# 60-hv-amp-soft-start.net
KiCad netlist of a schematic drawn in EAGLE
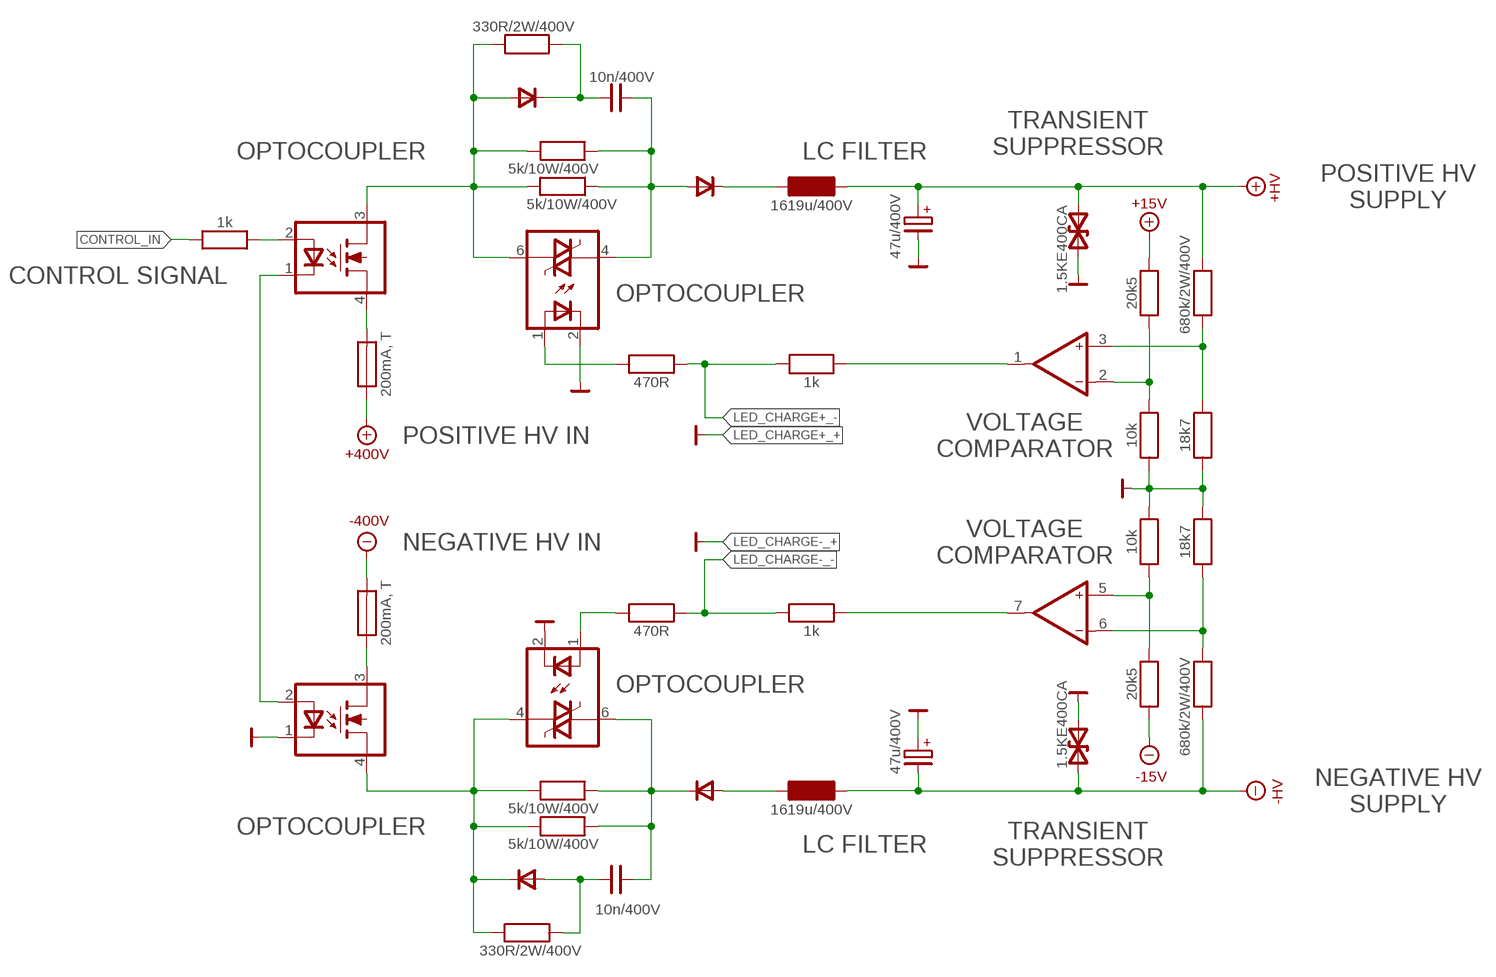
[diagram p0: schematic, sheet 1]

(export (version "E")
  (design (tool "Eeschema 10.0.6"))
  (components
    (comp (ref "C25")
      (value "10n/400V")
      (footprint "eagle-import:C03-CERAMIC-HV15-N")
      (libsource (lib "eagle-import") (part "C03-CERAMIC-HV15-N"))
    )
    (comp (ref "C26")
      (value "10n/400V")
      (footprint "eagle-import:C03-CERAMIC-HV15-N")
      (libsource (lib "eagle-import") (part "C03-CERAMIC-HV15-N"))
    )
    (comp (ref "C27")
      (value "47u/400V")
      (footprint "eagle-import:CE03-R18")
      (libsource (lib "eagle-import") (part "CE03-R18"))
    )
    (comp (ref "C28")
      (value "47u/400V")
      (footprint "eagle-import:CE03-R18")
      (libsource (lib "eagle-import") (part "CE03-R18"))
    )
    (comp (ref "D27")
      (value "UF4007")
      (footprint "eagle-import:D04N-DO41-VALUE")
      (libsource (lib "eagle-import") (part "D04B"))
    )
    (comp (ref "D28")
      (value "UF4007")
      (footprint "eagle-import:D04N-DO41-VALUE")
      (libsource (lib "eagle-import") (part "D04B"))
    )
    (comp (ref "D29")
      (value "UF4007")
      (footprint "eagle-import:D04N-DO41-VALUE")
      (libsource (lib "eagle-import") (part "D04B"))
    )
    (comp (ref "D30")
      (value "UF4007")
      (footprint "eagle-import:D04N-DO41-VALUE")
      (libsource (lib "eagle-import") (part "D04B"))
    )
    (comp (ref "D31")
      (value "1.5KE400CA")
      (footprint "eagle-import:DSB06N2")
      (libsource (lib "eagle-import") (part "DSB"))
    )
    (comp (ref "D32")
      (value "1.5KE400CA")
      (footprint "eagle-import:DSB06N2")
      (libsource (lib "eagle-import") (part "DSB"))
    )
    (comp (ref "F1")
      (value "200mA, T")
      (footprint "eagle-import:F02")
      (libsource (lib "eagle-import") (part "F"))
    )
    (comp (ref "F2")
      (value "200mA, T")
      (footprint "eagle-import:F02")
      (libsource (lib "eagle-import") (part "F"))
    )
    (comp (ref "L1")
      (value "1619u/400V")
      (footprint "eagle-import:L12-6X26")
      (libsource (lib "eagle-import") (part "L12-6X26"))
    )
    (comp (ref "L2")
      (value "1619u/400V")
      (footprint "eagle-import:L12-6X26")
      (libsource (lib "eagle-import") (part "L12-6X26"))
    )
    (comp (ref "N25")
      (value "AQZ204")
      (footprint "eagle-import:AQZ-N")
      (libsource (lib "eagle-import") (part "AQZ202"))
    )
    (comp (ref "N26")
      (value "AQZ204")
      (footprint "eagle-import:AQZ-N")
      (libsource (lib "eagle-import") (part "AQZ202"))
    )
    (comp (ref "N27")
      (value "IL420")
      (footprint "eagle-import:DIP06L")
      (libsource (lib "eagle-import") (part "IL420"))
    )
    (comp (ref "N28")
      (value "IL420")
      (footprint "eagle-import:DIP06L")
      (libsource (lib "eagle-import") (part "IL420"))
    )
    (comp (ref "N29")
      (value "OPA2277")
      (footprint "eagle-import:DIP08L")
      (libsource (lib "eagle-import") (part "OPA2277L"))
    )
    (comp (ref "R113")
      (value "1k")
      (footprint "eagle-import:R04N")
      (libsource (lib "eagle-import") (part "R04"))
    )
    (comp (ref "R114")
      (value "330R/2W/400V")
      (footprint "eagle-import:R06-2W")
      (libsource (lib "eagle-import") (part "R06-2W"))
    )
    (comp (ref "R115")
      (value "5k/10W/400V")
      (footprint "eagle-import:TO220-2A")
      (libsource (lib "eagle-import") (part "R02A"))
    )
    (comp (ref "R116")
      (value "5k/10W/400V")
      (footprint "eagle-import:TO220-2A")
      (libsource (lib "eagle-import") (part "R02A"))
    )
    (comp (ref "R117")
      (value "5k/10W/400V")
      (footprint "eagle-import:TO220-2A")
      (libsource (lib "eagle-import") (part "R02A"))
    )
    (comp (ref "R118")
      (value "5k/10W/400V")
      (footprint "eagle-import:TO220-2A")
      (libsource (lib "eagle-import") (part "R02A"))
    )
    (comp (ref "R119")
      (value "330R/2W/400V")
      (footprint "eagle-import:R06-2W")
      (libsource (lib "eagle-import") (part "R06-2W"))
    )
    (comp (ref "R120")
      (value "470R")
      (footprint "eagle-import:R04N")
      (libsource (lib "eagle-import") (part "R04N"))
    )
    (comp (ref "R121")
      (value "470R")
      (footprint "eagle-import:R04N")
      (libsource (lib "eagle-import") (part "R04N"))
    )
    (comp (ref "R122")
      (value "1k")
      (footprint "eagle-import:R04N")
      (libsource (lib "eagle-import") (part "R04N"))
    )
    (comp (ref "R123")
      (value "1k")
      (footprint "eagle-import:R04N")
      (libsource (lib "eagle-import") (part "R04N"))
    )
    (comp (ref "R124")
      (value "20k5")
      (footprint "eagle-import:R04N")
      (libsource (lib "eagle-import") (part "R04N"))
    )
    (comp (ref "R125")
      (value "10k")
      (footprint "eagle-import:R04N")
      (libsource (lib "eagle-import") (part "R"))
    )
    (comp (ref "R126")
      (value "10k")
      (footprint "eagle-import:R04N")
      (libsource (lib "eagle-import") (part "R04N"))
    )
    (comp (ref "R127")
      (value "20k5")
      (footprint "eagle-import:R04N")
      (libsource (lib "eagle-import") (part "R04N"))
    )
    (comp (ref "R128")
      (value "680k/2W/400V")
      (footprint "eagle-import:R06-2W")
      (libsource (lib "eagle-import") (part "R06-2W"))
    )
    (comp (ref "R129")
      (value "18k7")
      (footprint "eagle-import:R04N")
      (libsource (lib "eagle-import") (part "R04N"))
    )
    (comp (ref "R130")
      (value "18k7")
      (footprint "eagle-import:R04N")
      (libsource (lib "eagle-import") (part "R04N"))
    )
    (comp (ref "R131")
      (value "680k/2W/400V")
      (footprint "eagle-import:R06-2W")
      (libsource (lib "eagle-import") (part "R06-2W"))
    )
  )
  (nets
    (net (code "1") (name "CONTROL_IN") (class "Default")
      (node (ref "R113") (pin "1") (pinfunction "1_1") (pintype "passive"))
    )
    (net (code "2") (name "LED_CHARGE+_+") (class "Default")
      (node (ref "C27") (pin "-") (pinfunction "-_-") (pintype "passive"))
      (node (ref "C28") (pin "+") (pinfunction "+_+") (pintype "passive"))
      (node (ref "D31") (pin "1") (pinfunction "1_1") (pintype "passive"))
      (node (ref "D32") (pin "2") (pinfunction "2_2") (pintype "passive"))
      (node (ref "N26") (pin "1") (pinfunction "C_1") (pintype "passive"))
      (node (ref "N27") (pin "2") (pinfunction "C_2") (pintype "passive"))
      (node (ref "N28") (pin "2") (pinfunction "C_2") (pintype "passive"))
      (node (ref "R125") (pin "1") (pinfunction "1_1") (pintype "passive"))
      (node (ref "R126") (pin "2") (pinfunction "2_2") (pintype "passive"))
      (node (ref "R129") (pin "1") (pinfunction "1_1") (pintype "passive"))
      (node (ref "R130") (pin "2") (pinfunction "2_2") (pintype "passive"))
    )
    (net (code "3") (name "LED_CHARGE+_-") (class "Default")
      (node (ref "R120") (pin "2") (pinfunction "2_2") (pintype "passive"))
      (node (ref "R122") (pin "2") (pinfunction "2_2") (pintype "passive"))
    )
    (net (code "4") (name "LED_CHARGE-_-") (class "Default")
      (node (ref "R121") (pin "2") (pinfunction "2_2") (pintype "passive"))
      (node (ref "R123") (pin "2") (pinfunction "2_2") (pintype "passive"))
    )
    (net (code "5") (name "Net-(C25-Pad1)") (class "Default")
      (node (ref "C25") (pin "1") (pinfunction "1_1") (pintype "passive"))
      (node (ref "D28") (pin "A") (pinfunction "A_A") (pintype "passive"))
      (node (ref "R119") (pin "1") (pinfunction "1_1") (pintype "passive"))
    )
    (net (code "6") (name "Net-(C26-Pad1)") (class "Default")
      (node (ref "C26") (pin "1") (pinfunction "1_1") (pintype "passive"))
      (node (ref "D27") (pin "C") (pinfunction "C_C") (pintype "passive"))
      (node (ref "R114") (pin "2") (pinfunction "2_2") (pintype "passive"))
    )
    (net (code "7") (name "Net-(D29-PadC)") (class "Default")
      (node (ref "D29") (pin "C") (pinfunction "C_C") (pintype "passive"))
      (node (ref "L1") (pin "1") (pinfunction "1_1") (pintype "passive"))
    )
    (net (code "8") (name "Net-(D30-PadA)") (class "Default")
      (node (ref "D30") (pin "A") (pinfunction "A_A") (pintype "passive"))
      (node (ref "L2") (pin "1") (pinfunction "1_1") (pintype "passive"))
    )
    (net (code "9") (name "Net-(N25-A)") (class "Default")
      (node (ref "N25") (pin "2") (pinfunction "A_2") (pintype "passive"))
      (node (ref "R113") (pin "2") (pinfunction "2_2") (pintype "passive"))
    )
    (net (code "10") (name "Net-(N25-C)") (class "Default")
      (node (ref "N25") (pin "1") (pinfunction "C_1") (pintype "passive"))
      (node (ref "N26") (pin "2") (pinfunction "A_2") (pintype "passive"))
    )
    (net (code "11") (name "Net-(N25-OUT1)") (class "Default")
      (node (ref "D27") (pin "A") (pinfunction "A_A") (pintype "passive"))
      (node (ref "N25") (pin "3") (pinfunction "OUT1_3") (pintype "passive"))
      (node (ref "N27") (pin "6") (pinfunction "MT2_6") (pintype "passive"))
      (node (ref "R114") (pin "1") (pinfunction "1_1") (pintype "passive"))
      (node (ref "R115") (pin "1") (pinfunction "1_1") (pintype "passive"))
      (node (ref "R116") (pin "2") (pinfunction "2_2") (pintype "passive"))
    )
    (net (code "12") (name "Net-(N25-OUT2)") (class "Default")
      (node (ref "F1") (pin "2") (pinfunction "2_2") (pintype "passive"))
      (node (ref "N25") (pin "4") (pinfunction "OUT2_4") (pintype "passive"))
    )
    (net (code "13") (name "Net-(N26-OUT1)") (class "Default")
      (node (ref "F2") (pin "1") (pinfunction "1_1") (pintype "passive"))
      (node (ref "N26") (pin "3") (pinfunction "OUT1_3") (pintype "passive"))
    )
    (net (code "14") (name "Net-(N26-OUT2)") (class "Default")
      (node (ref "D28") (pin "C") (pinfunction "C_C") (pintype "passive"))
      (node (ref "N26") (pin "4") (pinfunction "OUT2_4") (pintype "passive"))
      (node (ref "N28") (pin "4") (pinfunction "MT1_4") (pintype "passive"))
      (node (ref "R117") (pin "2") (pinfunction "2_2") (pintype "passive"))
      (node (ref "R118") (pin "1") (pinfunction "1_1") (pintype "passive"))
      (node (ref "R119") (pin "2") (pinfunction "2_2") (pintype "passive"))
    )
    (net (code "15") (name "Net-(N27-A)") (class "Default")
      (node (ref "N27") (pin "1") (pinfunction "A_1") (pintype "passive"))
      (node (ref "R120") (pin "1") (pinfunction "1_1") (pintype "passive"))
    )
    (net (code "16") (name "Net-(N27-MT1)") (class "Default")
      (node (ref "C26") (pin "2") (pinfunction "2_2") (pintype "passive"))
      (node (ref "D29") (pin "A") (pinfunction "A_A") (pintype "passive"))
      (node (ref "N27") (pin "4") (pinfunction "MT1_4") (pintype "passive"))
      (node (ref "R115") (pin "2") (pinfunction "2_2") (pintype "passive"))
      (node (ref "R116") (pin "1") (pinfunction "1_1") (pintype "passive"))
    )
    (net (code "17") (name "Net-(N28-A)") (class "Default")
      (node (ref "N28") (pin "1") (pinfunction "A_1") (pintype "passive"))
      (node (ref "R121") (pin "1") (pinfunction "1_1") (pintype "passive"))
    )
    (net (code "18") (name "Net-(N28-MT2)") (class "Default")
      (node (ref "C25") (pin "2") (pinfunction "2_2") (pintype "passive"))
      (node (ref "D30") (pin "C") (pinfunction "C_C") (pintype "passive"))
      (node (ref "N28") (pin "6") (pinfunction "MT2_6") (pintype "passive"))
      (node (ref "R117") (pin "1") (pinfunction "1_1") (pintype "passive"))
      (node (ref "R118") (pin "2") (pinfunction "2_2") (pintype "passive"))
    )
    (net (code "19") (name "Net-(N29A-IN+)") (class "Default")
      (node (ref "N29") (pin "3") (pinfunction "IN+_3") (pintype "input"))
      (node (ref "R128") (pin "1") (pinfunction "1_1") (pintype "passive"))
      (node (ref "R129") (pin "2") (pinfunction "2_2") (pintype "passive"))
    )
    (net (code "20") (name "Net-(N29A-IN-)") (class "Default")
      (node (ref "N29") (pin "2") (pinfunction "IN-_2") (pintype "input"))
      (node (ref "R124") (pin "1") (pinfunction "1_1") (pintype "passive"))
      (node (ref "R125") (pin "2") (pinfunction "2_2") (pintype "passive"))
    )
    (net (code "21") (name "Net-(N29A-OUT)") (class "Default")
      (node (ref "N29") (pin "1") (pinfunction "OUT_1") (pintype "output"))
      (node (ref "R122") (pin "1") (pinfunction "1_1") (pintype "passive"))
    )
    (net (code "22") (name "Net-(N29B-IN+)") (class "Default")
      (node (ref "N29") (pin "5") (pinfunction "IN+_5") (pintype "input"))
      (node (ref "R126") (pin "1") (pinfunction "1_1") (pintype "passive"))
      (node (ref "R127") (pin "2") (pinfunction "2_2") (pintype "passive"))
    )
    (net (code "23") (name "Net-(N29B-IN-)") (class "Default")
      (node (ref "N29") (pin "6") (pinfunction "IN-_6") (pintype "input"))
      (node (ref "R130") (pin "1") (pinfunction "1_1") (pintype "passive"))
      (node (ref "R131") (pin "2") (pinfunction "2_2") (pintype "passive"))
    )
    (net (code "24") (name "Net-(N29B-OUT)") (class "Default")
      (node (ref "N29") (pin "7") (pinfunction "OUT_7") (pintype "output"))
      (node (ref "R123") (pin "1") (pinfunction "1_1") (pintype "passive"))
    )
    (net (code "25") (name "V+15V") (class "Default")
      (node (ref "R124") (pin "2") (pinfunction "2_2") (pintype "passive"))
    )
    (net (code "26") (name "V+400V") (class "Default")
      (node (ref "F1") (pin "1") (pinfunction "1_1") (pintype "passive"))
    )
    (net (code "27") (name "V+HV") (class "Default")
      (node (ref "C27") (pin "+") (pinfunction "+_+") (pintype "passive"))
      (node (ref "D31") (pin "2") (pinfunction "2_2") (pintype "passive"))
      (node (ref "L1") (pin "2") (pinfunction "2_2") (pintype "passive"))
      (node (ref "R128") (pin "2") (pinfunction "2_2") (pintype "passive"))
    )
    (net (code "28") (name "V-15V") (class "Default")
      (node (ref "R127") (pin "1") (pinfunction "1_1") (pintype "passive"))
    )
    (net (code "29") (name "V-400V") (class "Default")
      (node (ref "F2") (pin "2") (pinfunction "2_2") (pintype "passive"))
    )
    (net (code "30") (name "V-HV") (class "Default")
      (node (ref "C28") (pin "-") (pinfunction "-_-") (pintype "passive"))
      (node (ref "D32") (pin "1") (pinfunction "1_1") (pintype "passive"))
      (node (ref "L2") (pin "2") (pinfunction "2_2") (pintype "passive"))
      (node (ref "R131") (pin "1") (pinfunction "1_1") (pintype "passive"))
    )
  )
)
